# gatedriver_trafo_sma_compact_ACDC_balan.net
KiCad netlist of a schematic drawn in EAGLE
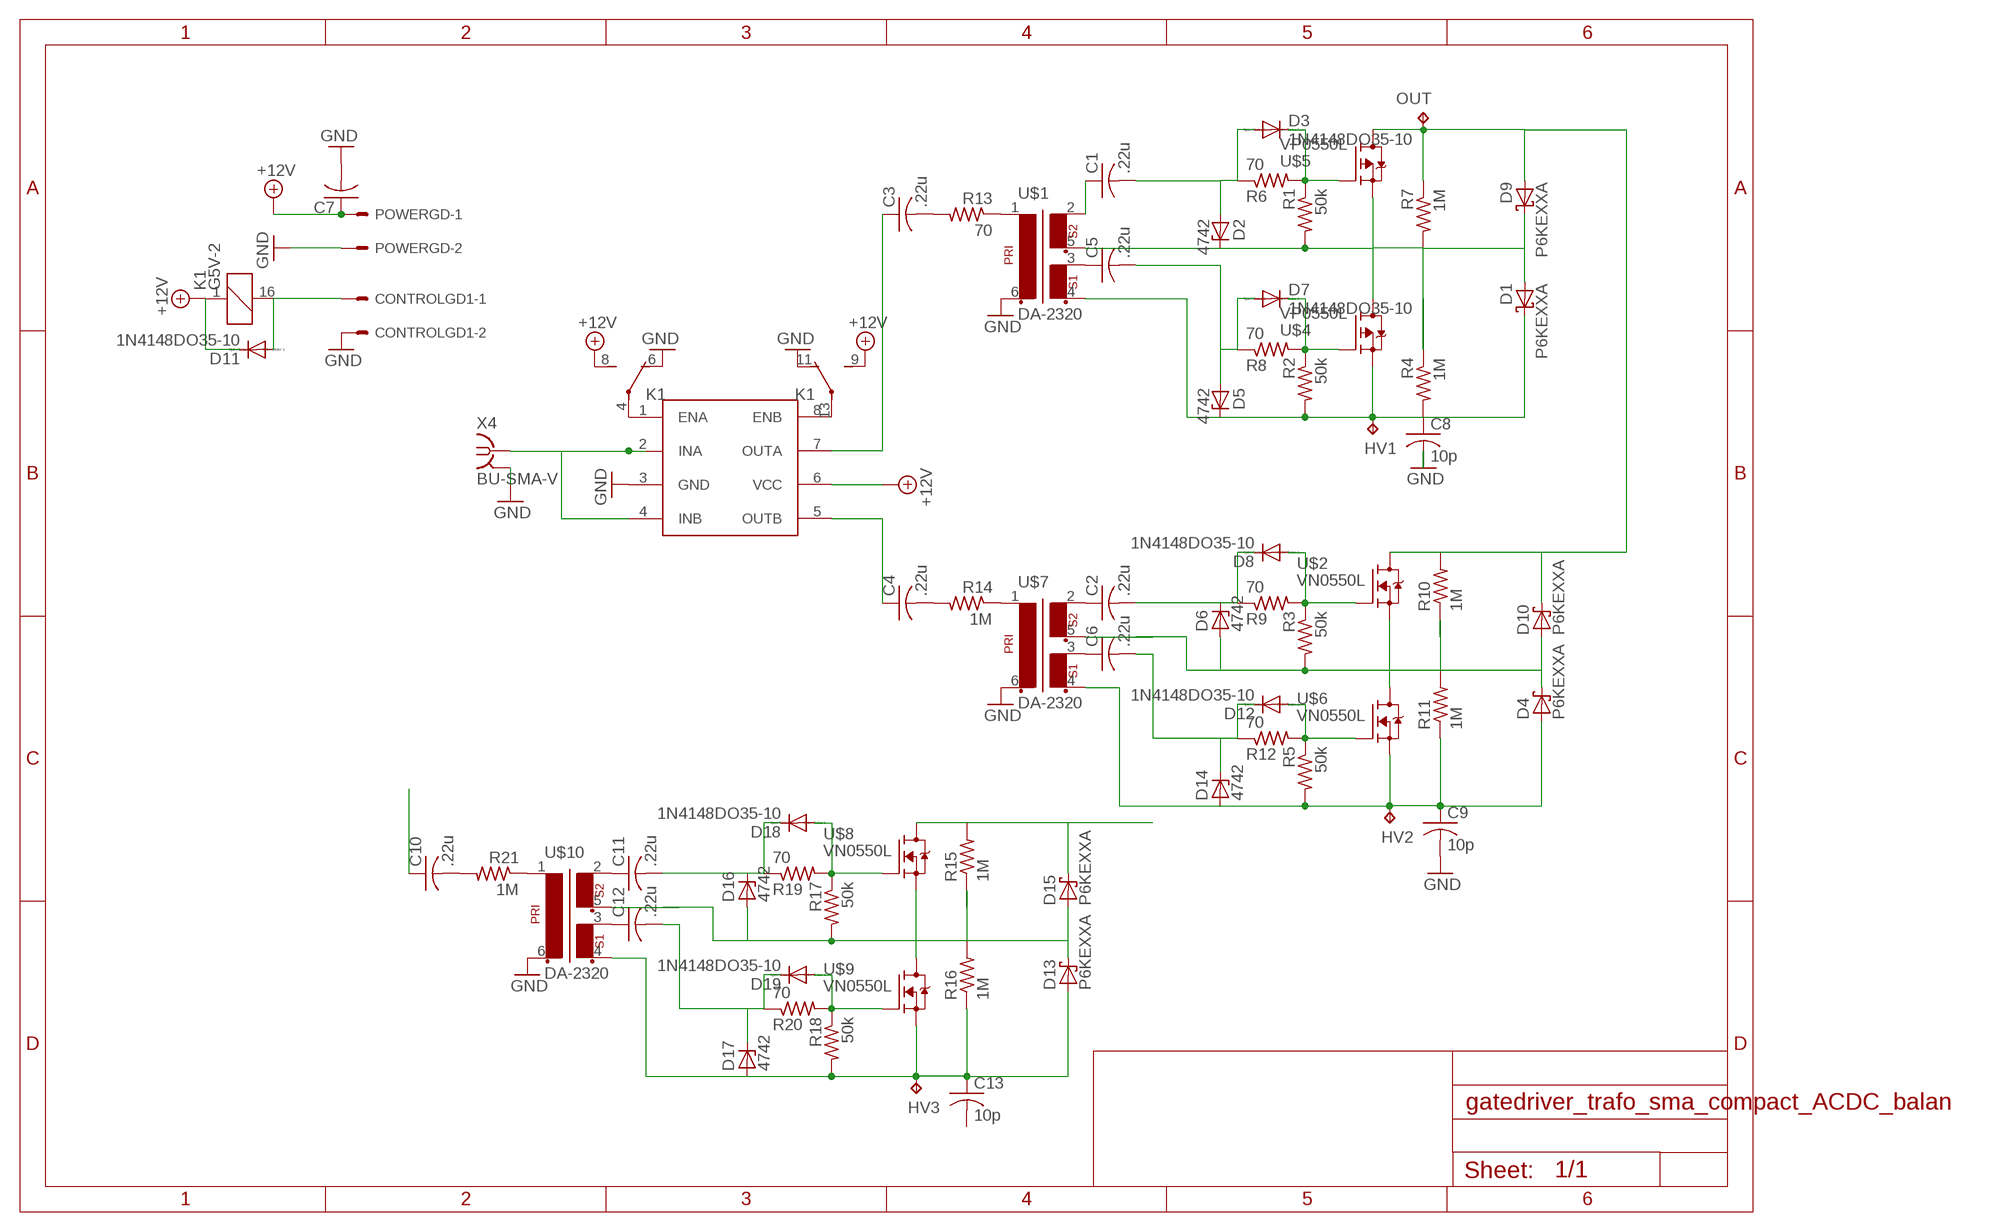
[diagram p0: schematic, sheet 1]

(export (version "E")
  (design (tool "Eeschema 10.0.6"))
  (components
    (comp (ref "C1")
      (value ".22u")
      (footprint "eagle-import:C050-055X075")
      (libsource (lib "eagle-import") (part "resistor_C-US050-055X075"))
    )
    (comp (ref "C2")
      (value ".22u")
      (footprint "eagle-import:C050-055X075")
      (libsource (lib "eagle-import") (part "resistor_C-US050-055X075"))
    )
    (comp (ref "C3")
      (value ".22u")
      (footprint "eagle-import:C050-055X075")
      (libsource (lib "eagle-import") (part "resistor_C-US050-055X075"))
    )
    (comp (ref "C4")
      (value ".22u")
      (footprint "eagle-import:C050-055X075")
      (libsource (lib "eagle-import") (part "resistor_C-US050-055X075"))
    )
    (comp (ref "C5")
      (value ".22u")
      (footprint "eagle-import:C050-055X075")
      (libsource (lib "eagle-import") (part "resistor_C-US050-055X075"))
    )
    (comp (ref "C6")
      (value ".22u")
      (footprint "eagle-import:C050-055X075")
      (libsource (lib "eagle-import") (part "resistor_C-US050-055X075"))
    )
    (comp (ref "C7")
      (value "C-US050-030X075")
      (footprint "eagle-import:C050-030X075")
      (libsource (lib "eagle-import") (part "C-US050-030X075"))
    )
    (comp (ref "C8")
      (value "10p")
      (footprint "eagle-import:C102-064X133")
      (libsource (lib "eagle-import") (part "resistor_C-US102-064X133"))
    )
    (comp (ref "C9")
      (value "10p")
      (footprint "eagle-import:C102-064X133")
      (libsource (lib "eagle-import") (part "resistor_C-US102-064X133"))
    )
    (comp (ref "C10")
      (value ".22u")
      (footprint "eagle-import:C050-055X075")
      (libsource (lib "eagle-import") (part "resistor_C-US050-055X075"))
    )
    (comp (ref "C11")
      (value ".22u")
      (footprint "eagle-import:C050-055X075")
      (libsource (lib "eagle-import") (part "resistor_C-US050-055X075"))
    )
    (comp (ref "C12")
      (value ".22u")
      (footprint "eagle-import:C050-055X075")
      (libsource (lib "eagle-import") (part "resistor_C-US050-055X075"))
    )
    (comp (ref "C13")
      (value "10p")
      (footprint "eagle-import:C102-064X133")
      (libsource (lib "eagle-import") (part "resistor_C-US102-064X133"))
    )
    (comp (ref "CONTROLGD1")
      (value "KK-156-2")
      (footprint "eagle-import:KK-156-2")
      (libsource (lib "eagle-import") (part "KK-156-2"))
    )
    (comp (ref "D1")
      (value "P6KEXXA")
      (footprint "eagle-import:C1702-15")
      (libsource (lib "eagle-import") (part "P6KEXXA"))
    )
    (comp (ref "D2")
      (value "4742")
      (footprint "eagle-import:ZDIO-10")
      (libsource (lib "eagle-import") (part "ZENER-DIODEZD-10"))
    )
    (comp (ref "D3")
      (value "1N4148DO35-10")
      (footprint "eagle-import:DO35-10")
      (libsource (lib "eagle-import") (part "1N4148DO35-10"))
    )
    (comp (ref "D4")
      (value "P6KEXXA")
      (footprint "eagle-import:C1702-15")
      (libsource (lib "eagle-import") (part "P6KEXXA"))
    )
    (comp (ref "D5")
      (value "4742")
      (footprint "eagle-import:ZDIO-10")
      (libsource (lib "eagle-import") (part "ZENER-DIODEZD-10"))
    )
    (comp (ref "D6")
      (value "4742")
      (footprint "eagle-import:ZDIO-10")
      (libsource (lib "eagle-import") (part "ZENER-DIODEZD-10"))
    )
    (comp (ref "D7")
      (value "1N4148DO35-10")
      (footprint "eagle-import:DO35-10")
      (libsource (lib "eagle-import") (part "1N4148DO35-10"))
    )
    (comp (ref "D8")
      (value "1N4148DO35-10")
      (footprint "eagle-import:DO35-10")
      (libsource (lib "eagle-import") (part "1N4148DO35-10"))
    )
    (comp (ref "D9")
      (value "P6KEXXA")
      (footprint "eagle-import:C1702-15")
      (libsource (lib "eagle-import") (part "P6KEXXA"))
    )
    (comp (ref "D10")
      (value "P6KEXXA")
      (footprint "eagle-import:C1702-15")
      (libsource (lib "eagle-import") (part "P6KEXXA"))
    )
    (comp (ref "D11")
      (value "1N4148DO35-10")
      (footprint "eagle-import:DO35-10")
      (libsource (lib "eagle-import") (part "1N4148DO35-10"))
    )
    (comp (ref "D12")
      (value "1N4148DO35-10")
      (footprint "eagle-import:DO35-10")
      (libsource (lib "eagle-import") (part "1N4148DO35-10"))
    )
    (comp (ref "D13")
      (value "P6KEXXA")
      (footprint "eagle-import:C1702-15")
      (libsource (lib "eagle-import") (part "P6KEXXA"))
    )
    (comp (ref "D14")
      (value "4742")
      (footprint "eagle-import:ZDIO-10")
      (libsource (lib "eagle-import") (part "ZENER-DIODEZD-10"))
    )
    (comp (ref "D15")
      (value "P6KEXXA")
      (footprint "eagle-import:C1702-15")
      (libsource (lib "eagle-import") (part "P6KEXXA"))
    )
    (comp (ref "D16")
      (value "4742")
      (footprint "eagle-import:ZDIO-10")
      (libsource (lib "eagle-import") (part "ZENER-DIODEZD-10"))
    )
    (comp (ref "D17")
      (value "4742")
      (footprint "eagle-import:ZDIO-10")
      (libsource (lib "eagle-import") (part "ZENER-DIODEZD-10"))
    )
    (comp (ref "D18")
      (value "1N4148DO35-10")
      (footprint "eagle-import:DO35-10")
      (libsource (lib "eagle-import") (part "1N4148DO35-10"))
    )
    (comp (ref "D19")
      (value "1N4148DO35-10")
      (footprint "eagle-import:DO35-10")
      (libsource (lib "eagle-import") (part "1N4148DO35-10"))
    )
    (comp (ref "HV1")
      (value "TPPAD1-20Y")
      (footprint "eagle-import:P1-20Y")
      (libsource (lib "eagle-import") (part "TPPAD1-20Y"))
    )
    (comp (ref "HV2")
      (value "TPPAD1-20Y")
      (footprint "eagle-import:P1-20Y")
      (libsource (lib "eagle-import") (part "TPPAD1-20Y"))
    )
    (comp (ref "HV3")
      (value "TPPAD1-20Y")
      (footprint "eagle-import:P1-20Y")
      (libsource (lib "eagle-import") (part "TPPAD1-20Y"))
    )
    (comp (ref "K1")
      (value "G5V-2")
      (footprint "eagle-import:G5V-2")
      (fields (field (name "MPN") "G5V-2 5DC"))
      (libsource (lib "eagle-import") (part "G5V-2"))
    )
    (comp (ref "OUT")
      (value "TPPAD1-20Y")
      (footprint "eagle-import:P1-20Y")
      (libsource (lib "eagle-import") (part "TPPAD1-20Y"))
    )
    (comp (ref "POWERGD")
      (value "KK-156-2")
      (footprint "eagle-import:KK-156-2")
      (libsource (lib "eagle-import") (part "KK-156-2"))
    )
    (comp (ref "R1")
      (value "50k")
      (footprint "eagle-import:0207_10")
      (libsource (lib "eagle-import") (part "R-US_0207/10"))
    )
    (comp (ref "R2")
      (value "50k")
      (footprint "eagle-import:0207_10")
      (libsource (lib "eagle-import") (part "R-US_0207/10"))
    )
    (comp (ref "R3")
      (value "50k")
      (footprint "eagle-import:0207_10")
      (libsource (lib "eagle-import") (part "R-US_0207/10"))
    )
    (comp (ref "R4")
      (value "1M")
      (footprint "eagle-import:0207_10")
      (libsource (lib "eagle-import") (part "R-US_0207/10"))
    )
    (comp (ref "R5")
      (value "50k")
      (footprint "eagle-import:0207_10")
      (libsource (lib "eagle-import") (part "R-US_0207/10"))
    )
    (comp (ref "R6")
      (value "70")
      (footprint "eagle-import:0207_10")
      (libsource (lib "eagle-import") (part "R-US_0207/10"))
    )
    (comp (ref "R7")
      (value "1M")
      (footprint "eagle-import:0207_10")
      (libsource (lib "eagle-import") (part "R-US_0207/10"))
    )
    (comp (ref "R8")
      (value "70")
      (footprint "eagle-import:0207_10")
      (libsource (lib "eagle-import") (part "R-US_0207/10"))
    )
    (comp (ref "R9")
      (value "70")
      (footprint "eagle-import:0207_10")
      (libsource (lib "eagle-import") (part "R-US_0207/10"))
    )
    (comp (ref "R10")
      (value "1M")
      (footprint "eagle-import:0207_10")
      (libsource (lib "eagle-import") (part "R-US_0207/10"))
    )
    (comp (ref "R11")
      (value "1M")
      (footprint "eagle-import:0207_10")
      (libsource (lib "eagle-import") (part "R-US_0207/10"))
    )
    (comp (ref "R12")
      (value "70")
      (footprint "eagle-import:0207_10")
      (libsource (lib "eagle-import") (part "R-US_0207/10"))
    )
    (comp (ref "R13")
      (value "70")
      (footprint "eagle-import:0207_10")
      (libsource (lib "eagle-import") (part "R-US_0207/10"))
    )
    (comp (ref "R14")
      (value "1M")
      (footprint "eagle-import:0207_10")
      (libsource (lib "eagle-import") (part "R-US_0207/10"))
    )
    (comp (ref "R15")
      (value "1M")
      (footprint "eagle-import:0207_10")
      (libsource (lib "eagle-import") (part "R-US_0207/10"))
    )
    (comp (ref "R16")
      (value "1M")
      (footprint "eagle-import:0207_10")
      (libsource (lib "eagle-import") (part "R-US_0207/10"))
    )
    (comp (ref "R17")
      (value "50k")
      (footprint "eagle-import:0207_10")
      (libsource (lib "eagle-import") (part "R-US_0207/10"))
    )
    (comp (ref "R18")
      (value "50k")
      (footprint "eagle-import:0207_10")
      (libsource (lib "eagle-import") (part "R-US_0207/10"))
    )
    (comp (ref "R19")
      (value "70")
      (footprint "eagle-import:0207_10")
      (libsource (lib "eagle-import") (part "R-US_0207/10"))
    )
    (comp (ref "R20")
      (value "70")
      (footprint "eagle-import:0207_10")
      (libsource (lib "eagle-import") (part "R-US_0207/10"))
    )
    (comp (ref "R21")
      (value "1M")
      (footprint "eagle-import:0207_10")
      (libsource (lib "eagle-import") (part "R-US_0207/10"))
    )
    (comp (ref "U$1")
      (value "DA-2320")
      (footprint "eagle-import:DIL06")
      (libsource (lib "eagle-import") (part "DA-2320"))
    )
    (comp (ref "U$2")
      (value "VN0550L")
      (footprint "eagle-import:TO92L")
      (libsource (lib "eagle-import") (part "VN0550L"))
    )
    (comp (ref "U$3")
      (value "UCC27425")
      (footprint "eagle-import:DIL08")
      (libsource (lib "eagle-import") (part "UCC27425"))
    )
    (comp (ref "U$4")
      (value "VP0550L")
      (footprint "eagle-import:TO92L")
      (libsource (lib "eagle-import") (part "VP0550L"))
    )
    (comp (ref "U$5")
      (value "VP0550L")
      (footprint "eagle-import:TO92L")
      (libsource (lib "eagle-import") (part "VP0550L"))
    )
    (comp (ref "U$6")
      (value "VN0550L")
      (footprint "eagle-import:TO92L")
      (libsource (lib "eagle-import") (part "VN0550L"))
    )
    (comp (ref "U$7")
      (value "DA-2320")
      (footprint "eagle-import:DIL06")
      (libsource (lib "eagle-import") (part "DA-2320"))
    )
    (comp (ref "U$8")
      (value "VN0550L")
      (footprint "eagle-import:TO92L")
      (libsource (lib "eagle-import") (part "VN0550L"))
    )
    (comp (ref "U$9")
      (value "VN0550L")
      (footprint "eagle-import:TO92L")
      (libsource (lib "eagle-import") (part "VN0550L"))
    )
    (comp (ref "U$10")
      (value "DA-2320")
      (footprint "eagle-import:DIL06")
      (libsource (lib "eagle-import") (part "DA-2320"))
    )
    (comp (ref "X4")
      (value "BU-SMA-V")
      (footprint "eagle-import:BU-SMA-V")
      (libsource (lib "eagle-import") (part "BU-SMA-V"))
    )
  )
  (nets
    (net (code "1") (name "+12V") (class "Default")
      (node (ref "C7") (pin "1") (pinfunction "1_1") (pintype "passive"))
      (node (ref "D11") (pin "C") (pinfunction "C_C") (pintype "passive"))
      (node (ref "K1") (pin "1") (pinfunction "1_1") (pintype "passive"))
      (node (ref "K1") (pin "8") (pinfunction "S_8") (pintype "passive"))
      (node (ref "K1") (pin "9") (pinfunction "S_9") (pintype "passive"))
      (node (ref "POWERGD") (pin "1") (pinfunction "S_1") (pintype "passive"))
      (node (ref "U$3") (pin "6") (pinfunction "VCC_6") (pintype "bidirectional"))
    )
    (net (code "2") (name "GND") (class "Default")
      (node (ref "C7") (pin "2") (pinfunction "2_2") (pintype "passive"))
      (node (ref "C8") (pin "2") (pinfunction "2_2") (pintype "passive"))
      (node (ref "C9") (pin "2") (pinfunction "2_2") (pintype "passive"))
      (node (ref "CONTROLGD1") (pin "2") (pinfunction "S_2") (pintype "passive"))
      (node (ref "K1") (pin "11") (pinfunction "O_11") (pintype "passive"))
      (node (ref "K1") (pin "6") (pinfunction "O_6") (pintype "passive"))
      (node (ref "POWERGD") (pin "2") (pinfunction "S_2") (pintype "passive"))
      (node (ref "U$1") (pin "6") (pinfunction "2_6") (pintype "passive"))
      (node (ref "U$10") (pin "6") (pinfunction "2_6") (pintype "passive"))
      (node (ref "U$3") (pin "3") (pinfunction "GND_3") (pintype "bidirectional"))
      (node (ref "U$7") (pin "6") (pinfunction "2_6") (pintype "passive"))
      (node (ref "X4") (pin "2") (pinfunction "2_2") (pintype "passive"))
      (node (ref "X4") (pin "3") (pinfunction "2_3") (pintype "passive"))
      (node (ref "X4") (pin "4") (pinfunction "2_4") (pintype "passive"))
      (node (ref "X4") (pin "5") (pinfunction "2_5") (pintype "passive"))
    )
    (net (code "3") (name "Net-(C1-Pad2)") (class "Default")
      (node (ref "C1") (pin "2") (pinfunction "2_2") (pintype "passive"))
      (node (ref "D2") (pin "A") (pinfunction "A_A") (pintype "passive"))
      (node (ref "D3") (pin "A") (pinfunction "A_A") (pintype "passive"))
      (node (ref "R6") (pin "1") (pinfunction "1_1") (pintype "passive"))
    )
    (net (code "4") (name "Net-(C2-Pad2)") (class "Default")
      (node (ref "C2") (pin "2") (pinfunction "2_2") (pintype "passive"))
      (node (ref "D6") (pin "C") (pinfunction "C_C") (pintype "passive"))
      (node (ref "D8") (pin "C") (pinfunction "C_C") (pintype "passive"))
      (node (ref "R9") (pin "1") (pinfunction "1_1") (pintype "passive"))
    )
    (net (code "5") (name "Net-(C3-Pad2)") (class "Default")
      (node (ref "C3") (pin "2") (pinfunction "2_2") (pintype "passive"))
      (node (ref "R13") (pin "2") (pinfunction "2_2") (pintype "passive"))
    )
    (net (code "6") (name "Net-(C4-Pad2)") (class "Default")
      (node (ref "C4") (pin "2") (pinfunction "2_2") (pintype "passive"))
      (node (ref "R14") (pin "2") (pinfunction "2_2") (pintype "passive"))
    )
    (net (code "7") (name "Net-(C5-Pad2)") (class "Default")
      (node (ref "C5") (pin "2") (pinfunction "2_2") (pintype "passive"))
      (node (ref "D5") (pin "A") (pinfunction "A_A") (pintype "passive"))
      (node (ref "D7") (pin "A") (pinfunction "A_A") (pintype "passive"))
      (node (ref "R8") (pin "1") (pinfunction "1_1") (pintype "passive"))
    )
    (net (code "8") (name "Net-(C6-Pad2)") (class "Default")
      (node (ref "C6") (pin "2") (pinfunction "2_2") (pintype "passive"))
      (node (ref "D12") (pin "C") (pinfunction "C_C") (pintype "passive"))
      (node (ref "D14") (pin "C") (pinfunction "C_C") (pintype "passive"))
      (node (ref "R12") (pin "1") (pinfunction "1_1") (pintype "passive"))
    )
    (net (code "9") (name "Net-(C10-Pad2)") (class "Default")
      (node (ref "C10") (pin "2") (pinfunction "2_2") (pintype "passive"))
      (node (ref "R21") (pin "2") (pinfunction "2_2") (pintype "passive"))
    )
    (net (code "10") (name "Net-(C11-Pad2)") (class "Default")
      (node (ref "C11") (pin "2") (pinfunction "2_2") (pintype "passive"))
      (node (ref "D16") (pin "C") (pinfunction "C_C") (pintype "passive"))
      (node (ref "D18") (pin "C") (pinfunction "C_C") (pintype "passive"))
      (node (ref "R19") (pin "1") (pinfunction "1_1") (pintype "passive"))
    )
    (net (code "11") (name "Net-(C12-Pad2)") (class "Default")
      (node (ref "C12") (pin "2") (pinfunction "2_2") (pintype "passive"))
      (node (ref "D17") (pin "C") (pinfunction "C_C") (pintype "passive"))
      (node (ref "D19") (pin "C") (pinfunction "C_C") (pintype "passive"))
      (node (ref "R20") (pin "1") (pinfunction "1_1") (pintype "passive"))
    )
    (net (code "12") (name "Net-(CONTROLGD1A-S)") (class "Default")
      (node (ref "CONTROLGD1") (pin "1") (pinfunction "S_1") (pintype "passive"))
      (node (ref "D11") (pin "A") (pinfunction "A_A") (pintype "passive"))
      (node (ref "K1") (pin "16") (pinfunction "2_16") (pintype "passive"))
    )
    (net (code "13") (name "Net-(K1A-P)") (class "Default")
      (node (ref "K1") (pin "4") (pinfunction "P_4") (pintype "passive"))
      (node (ref "U$3") (pin "1") (pinfunction "ENA_1") (pintype "bidirectional"))
    )
    (net (code "14") (name "Net-(K1B-P)") (class "Default")
      (node (ref "K1") (pin "13") (pinfunction "P_13") (pintype "passive"))
      (node (ref "U$3") (pin "8") (pinfunction "ENB_8") (pintype "bidirectional"))
    )
    (net (code "15") (name "Net-(R13-Pad1)") (class "Default")
      (node (ref "R13") (pin "1") (pinfunction "1_1") (pintype "passive"))
      (node (ref "U$1") (pin "1") (pinfunction "1_1") (pintype "passive"))
    )
    (net (code "16") (name "Net-(R14-Pad1)") (class "Default")
      (node (ref "R14") (pin "1") (pinfunction "1_1") (pintype "passive"))
      (node (ref "U$7") (pin "1") (pinfunction "1_1") (pintype "passive"))
    )
    (net (code "17") (name "Net-(R21-Pad1)") (class "Default")
      (node (ref "R21") (pin "1") (pinfunction "1_1") (pintype "passive"))
      (node (ref "U$10") (pin "1") (pinfunction "1_1") (pintype "passive"))
    )
    (net (code "18") (name "Net-(U$1-3)") (class "Default")
      (node (ref "C8") (pin "1") (pinfunction "1_1") (pintype "passive"))
      (node (ref "D1") (pin "C") (pinfunction "C_C") (pintype "passive"))
      (node (ref "D5") (pin "C") (pinfunction "C_C") (pintype "passive"))
      (node (ref "HV1") (pin "TP") (pinfunction "TP_TP") (pintype "input"))
      (node (ref "R2") (pin "2") (pinfunction "2_2") (pintype "passive"))
      (node (ref "R4") (pin "2") (pinfunction "2_2") (pintype "passive"))
      (node (ref "U$1") (pin "4") (pinfunction "3_4") (pintype "passive"))
      (node (ref "U$4") (pin "3") (pinfunction "S_3") (pintype "passive"))
    )
    (net (code "19") (name "Net-(U$1-4)") (class "Default")
      (node (ref "C5") (pin "1") (pinfunction "1_1") (pintype "passive"))
      (node (ref "U$1") (pin "3") (pinfunction "4_3") (pintype "passive"))
    )
    (net (code "20") (name "Net-(U$1-6)") (class "Default")
      (node (ref "C1") (pin "1") (pinfunction "1_1") (pintype "passive"))
      (node (ref "U$1") (pin "2") (pinfunction "6_2") (pintype "passive"))
    )
    (net (code "21") (name "Net-(U$2-D)") (class "Default")
      (node (ref "D10") (pin "C") (pinfunction "C_C") (pintype "passive"))
      (node (ref "D9") (pin "A") (pinfunction "A_A") (pintype "passive"))
      (node (ref "OUT") (pin "TP") (pinfunction "TP_TP") (pintype "input"))
      (node (ref "R10") (pin "2") (pinfunction "2_2") (pintype "passive"))
      (node (ref "R7") (pin "1") (pinfunction "1_1") (pintype "passive"))
      (node (ref "U$2") (pin "1") (pinfunction "D_1") (pintype "passive"))
      (node (ref "U$5") (pin "1") (pinfunction "D_1") (pintype "passive"))
    )
    (net (code "22") (name "Net-(U$2-G)") (class "Default")
      (node (ref "D8") (pin "A") (pinfunction "A_A") (pintype "passive"))
      (node (ref "R3") (pin "1") (pinfunction "1_1") (pintype "passive"))
      (node (ref "R9") (pin "2") (pinfunction "2_2") (pintype "passive"))
      (node (ref "U$2") (pin "2") (pinfunction "G_2") (pintype "passive"))
    )
    (net (code "23") (name "Net-(U$2-S)") (class "Default")
      (node (ref "D10") (pin "A") (pinfunction "A_A") (pintype "passive"))
      (node (ref "D4") (pin "C") (pinfunction "C_C") (pintype "passive"))
      (node (ref "D6") (pin "A") (pinfunction "A_A") (pintype "passive"))
      (node (ref "R10") (pin "1") (pinfunction "1_1") (pintype "passive"))
      (node (ref "R11") (pin "2") (pinfunction "2_2") (pintype "passive"))
      (node (ref "R3") (pin "2") (pinfunction "2_2") (pintype "passive"))
      (node (ref "U$2") (pin "3") (pinfunction "S_3") (pintype "passive"))
      (node (ref "U$6") (pin "1") (pinfunction "D_1") (pintype "passive"))
    )
    (net (code "24") (name "Net-(U$3-INA)") (class "Default")
      (node (ref "U$3") (pin "2") (pinfunction "INA_2") (pintype "bidirectional"))
      (node (ref "U$3") (pin "4") (pinfunction "INB_4") (pintype "bidirectional"))
      (node (ref "X4") (pin "1") (pinfunction "1_1") (pintype "passive"))
    )
    (net (code "25") (name "Net-(U$3-OUTA)") (class "Default")
      (node (ref "C3") (pin "1") (pinfunction "1_1") (pintype "passive"))
      (node (ref "U$3") (pin "7") (pinfunction "OUTA_7") (pintype "bidirectional"))
    )
    (net (code "26") (name "Net-(U$3-OUTB)") (class "Default")
      (node (ref "C4") (pin "1") (pinfunction "1_1") (pintype "passive"))
      (node (ref "U$3") (pin "5") (pinfunction "OUTB_5") (pintype "bidirectional"))
    )
    (net (code "27") (name "Net-(U$4-D)") (class "Default")
      (node (ref "D1") (pin "A") (pinfunction "A_A") (pintype "passive"))
      (node (ref "D2") (pin "C") (pinfunction "C_C") (pintype "passive"))
      (node (ref "D9") (pin "C") (pinfunction "C_C") (pintype "passive"))
      (node (ref "R1") (pin "2") (pinfunction "2_2") (pintype "passive"))
      (node (ref "R4") (pin "1") (pinfunction "1_1") (pintype "passive"))
      (node (ref "R7") (pin "2") (pinfunction "2_2") (pintype "passive"))
      (node (ref "U$1") (pin "5") (pinfunction "5_5") (pintype "passive"))
      (node (ref "U$4") (pin "1") (pinfunction "D_1") (pintype "passive"))
      (node (ref "U$5") (pin "3") (pinfunction "S_3") (pintype "passive"))
    )
    (net (code "28") (name "Net-(U$4-G)") (class "Default")
      (node (ref "D7") (pin "C") (pinfunction "C_C") (pintype "passive"))
      (node (ref "R2") (pin "1") (pinfunction "1_1") (pintype "passive"))
      (node (ref "R8") (pin "2") (pinfunction "2_2") (pintype "passive"))
      (node (ref "U$4") (pin "2") (pinfunction "G_2") (pintype "passive"))
    )
    (net (code "29") (name "Net-(U$5-G)") (class "Default")
      (node (ref "D3") (pin "C") (pinfunction "C_C") (pintype "passive"))
      (node (ref "R1") (pin "1") (pinfunction "1_1") (pintype "passive"))
      (node (ref "R6") (pin "2") (pinfunction "2_2") (pintype "passive"))
      (node (ref "U$5") (pin "2") (pinfunction "G_2") (pintype "passive"))
    )
    (net (code "30") (name "Net-(U$6-G)") (class "Default")
      (node (ref "D12") (pin "A") (pinfunction "A_A") (pintype "passive"))
      (node (ref "R12") (pin "2") (pinfunction "2_2") (pintype "passive"))
      (node (ref "R5") (pin "1") (pinfunction "1_1") (pintype "passive"))
      (node (ref "U$6") (pin "2") (pinfunction "G_2") (pintype "passive"))
    )
    (net (code "31") (name "Net-(U$6-S)") (class "Default")
      (node (ref "C9") (pin "1") (pinfunction "1_1") (pintype "passive"))
      (node (ref "D14") (pin "A") (pinfunction "A_A") (pintype "passive"))
      (node (ref "D4") (pin "A") (pinfunction "A_A") (pintype "passive"))
      (node (ref "HV2") (pin "TP") (pinfunction "TP_TP") (pintype "input"))
      (node (ref "R11") (pin "1") (pinfunction "1_1") (pintype "passive"))
      (node (ref "R5") (pin "2") (pinfunction "2_2") (pintype "passive"))
      (node (ref "U$6") (pin "3") (pinfunction "S_3") (pintype "passive"))
      (node (ref "U$7") (pin "4") (pinfunction "3_4") (pintype "passive"))
    )
    (net (code "32") (name "Net-(U$7-4)") (class "Default")
      (node (ref "C6") (pin "1") (pinfunction "1_1") (pintype "passive"))
      (node (ref "U$7") (pin "3") (pinfunction "4_3") (pintype "passive"))
    )
    (net (code "33") (name "Net-(U$7-6)") (class "Default")
      (node (ref "C2") (pin "1") (pinfunction "1_1") (pintype "passive"))
      (node (ref "U$7") (pin "2") (pinfunction "6_2") (pintype "passive"))
    )
    (net (code "34") (name "Net-(U$8-D)") (class "Default")
      (node (ref "D15") (pin "C") (pinfunction "C_C") (pintype "passive"))
      (node (ref "R15") (pin "2") (pinfunction "2_2") (pintype "passive"))
      (node (ref "U$8") (pin "1") (pinfunction "D_1") (pintype "passive"))
    )
    (net (code "35") (name "Net-(U$8-G)") (class "Default")
      (node (ref "D18") (pin "A") (pinfunction "A_A") (pintype "passive"))
      (node (ref "R17") (pin "1") (pinfunction "1_1") (pintype "passive"))
      (node (ref "R19") (pin "2") (pinfunction "2_2") (pintype "passive"))
      (node (ref "U$8") (pin "2") (pinfunction "G_2") (pintype "passive"))
    )
    (net (code "36") (name "Net-(U$8-S)") (class "Default")
      (node (ref "D13") (pin "C") (pinfunction "C_C") (pintype "passive"))
      (node (ref "D15") (pin "A") (pinfunction "A_A") (pintype "passive"))
      (node (ref "D16") (pin "A") (pinfunction "A_A") (pintype "passive"))
      (node (ref "R15") (pin "1") (pinfunction "1_1") (pintype "passive"))
      (node (ref "R16") (pin "2") (pinfunction "2_2") (pintype "passive"))
      (node (ref "R17") (pin "2") (pinfunction "2_2") (pintype "passive"))
      (node (ref "U$8") (pin "3") (pinfunction "S_3") (pintype "passive"))
      (node (ref "U$9") (pin "1") (pinfunction "D_1") (pintype "passive"))
    )
    (net (code "37") (name "Net-(U$9-G)") (class "Default")
      (node (ref "D19") (pin "A") (pinfunction "A_A") (pintype "passive"))
      (node (ref "R18") (pin "1") (pinfunction "1_1") (pintype "passive"))
      (node (ref "R20") (pin "2") (pinfunction "2_2") (pintype "passive"))
      (node (ref "U$9") (pin "2") (pinfunction "G_2") (pintype "passive"))
    )
    (net (code "38") (name "Net-(U$10-3)") (class "Default")
      (node (ref "C13") (pin "1") (pinfunction "1_1") (pintype "passive"))
      (node (ref "D13") (pin "A") (pinfunction "A_A") (pintype "passive"))
      (node (ref "D17") (pin "A") (pinfunction "A_A") (pintype "passive"))
      (node (ref "HV3") (pin "TP") (pinfunction "TP_TP") (pintype "input"))
      (node (ref "R16") (pin "1") (pinfunction "1_1") (pintype "passive"))
      (node (ref "R18") (pin "2") (pinfunction "2_2") (pintype "passive"))
      (node (ref "U$10") (pin "4") (pinfunction "3_4") (pintype "passive"))
      (node (ref "U$9") (pin "3") (pinfunction "S_3") (pintype "passive"))
    )
    (net (code "39") (name "Net-(U$10-4)") (class "Default")
      (node (ref "C12") (pin "1") (pinfunction "1_1") (pintype "passive"))
      (node (ref "U$10") (pin "3") (pinfunction "4_3") (pintype "passive"))
    )
    (net (code "40") (name "Net-(U$10-6)") (class "Default")
      (node (ref "C11") (pin "1") (pinfunction "1_1") (pintype "passive"))
      (node (ref "U$10") (pin "2") (pinfunction "6_2") (pintype "passive"))
    )
    (net (code "41") (name "unconnected-(C10-Pad1)") (class "Default")
      (node (ref "C10") (pin "1") (pinfunction "1_1") (pintype "passive"))
    )
    (net (code "42") (name "unconnected-(C13-Pad2)") (class "Default")
      (node (ref "C13") (pin "2") (pinfunction "2_2") (pintype "passive"))
    )
    (net (code "43") (name "unconnected-(U$7-Pad5)") (class "Default")
      (node (ref "U$7") (pin "5") (pinfunction "5_5") (pintype "passive"))
    )
    (net (code "44") (name "unconnected-(U$10-Pad5)") (class "Default")
      (node (ref "U$10") (pin "5") (pinfunction "5_5") (pintype "passive"))
    )
  )
)
